# Hitachi_wind_main.net
KiCad netlist of a schematic drawn in Altium Designer
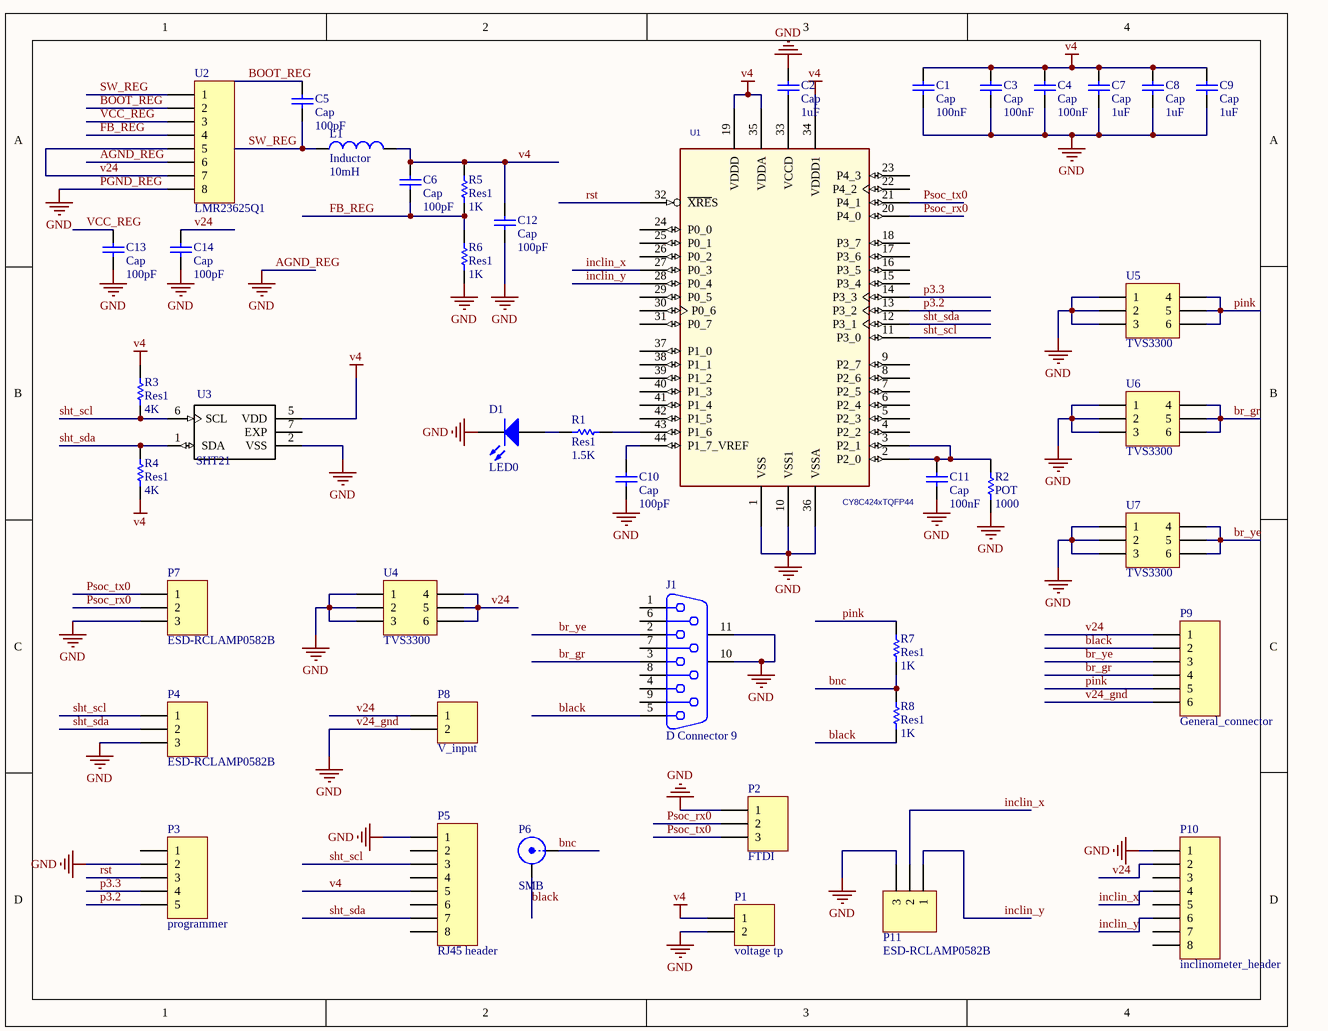
[diagram p0: Hitachi_wind_main.SchDoc]

(export (version "E")
  (design (tool "Eeschema 10.0.6"))
  (components
    (comp (ref "C1")
      (value "Cap")
      (footprint "Miscellaneous Devices:1608[0603]")
      (description "Capacitor")
      (fields (field (name "ALTIUM_VALUE") "100nF") (field (name "PUBLISHER") "Altium Limited"))
      (libsource (lib "Miscellaneous Devices") (part "Cap"))
    )
    (comp (ref "C2")
      (value "Cap")
      (footprint "Miscellaneous Devices:1608[0603]")
      (description "Capacitor")
      (fields (field (name "ALTIUM_VALUE") "1uF") (field (name "PUBLISHER") "Altium Limited"))
      (libsource (lib "Miscellaneous Devices") (part "Cap"))
    )
    (comp (ref "C3")
      (value "Cap")
      (footprint "Miscellaneous Devices:1608[0603]")
      (description "Capacitor")
      (fields (field (name "ALTIUM_VALUE") "100nF") (field (name "PUBLISHER") "Altium Limited"))
      (libsource (lib "Miscellaneous Devices") (part "Cap"))
    )
    (comp (ref "C4")
      (value "Cap")
      (footprint "Miscellaneous Devices:1608[0603]")
      (description "Capacitor")
      (fields (field (name "ALTIUM_VALUE") "100nF") (field (name "PUBLISHER") "Altium Limited"))
      (libsource (lib "Miscellaneous Devices") (part "Cap"))
    )
    (comp (ref "C5")
      (value "Cap")
      (footprint "Miscellaneous Devices:1608[0603]")
      (description "Capacitor")
      (fields (field (name "ALTIUM_VALUE") "100pF") (field (name "PUBLISHER") "Altium Limited"))
      (libsource (lib "Miscellaneous Devices") (part "Cap"))
    )
    (comp (ref "C6")
      (value "Cap")
      (footprint "Miscellaneous Devices:1608[0603]")
      (description "Capacitor")
      (fields (field (name "ALTIUM_VALUE") "100pF") (field (name "PUBLISHER") "Altium Limited"))
      (libsource (lib "Miscellaneous Devices") (part "Cap"))
    )
    (comp (ref "C7")
      (value "Cap")
      (footprint "Miscellaneous Devices:1608[0603]")
      (description "Capacitor")
      (fields (field (name "ALTIUM_VALUE") "1uF") (field (name "PUBLISHER") "Altium Limited"))
      (libsource (lib "Miscellaneous Devices") (part "Cap"))
    )
    (comp (ref "C8")
      (value "Cap")
      (footprint "Miscellaneous Devices:1608[0603]")
      (description "Capacitor")
      (fields (field (name "ALTIUM_VALUE") "1uF") (field (name "PUBLISHER") "Altium Limited"))
      (libsource (lib "Miscellaneous Devices") (part "Cap"))
    )
    (comp (ref "C9")
      (value "Cap")
      (footprint "Miscellaneous Devices:1608[0603]")
      (description "Capacitor")
      (fields (field (name "ALTIUM_VALUE") "1uF") (field (name "PUBLISHER") "Altium Limited"))
      (libsource (lib "Miscellaneous Devices") (part "Cap"))
    )
    (comp (ref "C10")
      (value "Cap")
      (footprint "Miscellaneous Devices:1608[0603]")
      (description "Capacitor")
      (fields (field (name "ALTIUM_VALUE") "100pF") (field (name "PUBLISHER") "Altium Limited"))
      (libsource (lib "Miscellaneous Devices") (part "Cap"))
    )
    (comp (ref "C11")
      (value "Cap")
      (footprint "Miscellaneous Devices:1608[0603]")
      (description "Capacitor")
      (fields (field (name "ALTIUM_VALUE") "100nF") (field (name "PUBLISHER") "Altium Limited"))
      (libsource (lib "Miscellaneous Devices") (part "Cap"))
    )
    (comp (ref "C12")
      (value "Cap")
      (footprint "Miscellaneous Devices:1608[0603]")
      (description "Capacitor")
      (fields (field (name "ALTIUM_VALUE") "100pF") (field (name "PUBLISHER") "Altium Limited"))
      (libsource (lib "Miscellaneous Devices") (part "Cap"))
    )
    (comp (ref "C13")
      (value "Cap")
      (footprint "Miscellaneous Devices:1608[0603]")
      (description "Capacitor")
      (fields (field (name "ALTIUM_VALUE") "100pF") (field (name "PUBLISHER") "Altium Limited"))
      (libsource (lib "Miscellaneous Devices") (part "Cap"))
    )
    (comp (ref "C14")
      (value "Cap")
      (footprint "Miscellaneous Devices:1608[0603]")
      (description "Capacitor")
      (fields (field (name "ALTIUM_VALUE") "100pF") (field (name "PUBLISHER") "Altium Limited"))
      (libsource (lib "Miscellaneous Devices") (part "Cap"))
    )
    (comp (ref "D1")
      (value "LED0")
      (footprint "3.2X1.6X1.1")
      (description "Typical INFRARED GaAs LED")
      (fields (field (name "PUBLISHER") "Altium Limited"))
      (libsource (lib "Miscellaneous Devices") (part "LED0"))
    )
    (comp (ref "J1")
      (value "D Connector 9")
      (footprint "DSUB1.385-2H9")
      (description "Receptacle Assembly, 9 Position, Right Angle")
      (fields (field (name "PUBLISHER") "Altium Limited"))
      (libsource (lib "Miscellaneous Connectors") (part "D Connector 9"))
    )
    (comp (ref "L1")
      (value "Inductor")
      (footprint "0402-A")
      (fields (field (name "ALTIUM_VALUE") "10mH") (field (name "PUBLISHER") "Altium Limited"))
      (libsource (lib "Miscellaneous Devices") (part "Inductor"))
    )
    (comp (ref "P1")
      (value "voltage tp")
      (footprint "HDR1X2")
      (description "Header, 2-Pin")
      (fields (field (name "PUBLISHER") "Altium Limited"))
      (libsource (lib "Miscellaneous Connectors") (part "Header 2"))
    )
    (comp (ref "P2")
      (value "FTDI")
      (footprint "HDR1X3")
      (description "Header, 3-Pin")
      (fields (field (name "PUBLISHER") "Altium Limited"))
      (libsource (lib "") (part "Header 3_1"))
    )
    (comp (ref "P3")
      (value "programmer")
      (footprint "HDR1X5")
      (description "Header, 5-Pin")
      (fields (field (name "PUBLISHER") "Altium Limited"))
      (libsource (lib "Miscellaneous Connectors") (part "Header 5"))
    )
    (comp (ref "P4")
      (value "ESD-RCLAMP0582B")
      (footprint "SC75:SC75")
      (description "Header, 3-Pin")
      (fields (field (name "PUBLISHER") "Altium Limited"))
      (libsource (lib "") (part "Header 3_1"))
    )
    (comp (ref "P5")
      (value "RJ45 header")
      (footprint "RJ-45 Header:RJ-45 Header")
      (description "Header, 8-Pin")
      (fields (field (name "PUBLISHER") "Altium Limited"))
      (libsource (lib "Miscellaneous Connectors") (part "Header 8"))
    )
    (comp (ref "P6")
      (value "SMB")
      (footprint "SMB_V-RJ45")
      (description "SMB Straight Connector")
      (fields (field (name "PUBLISHER") "Altium Limited"))
      (libsource (lib "Miscellaneous Connectors") (part "SMB"))
    )
    (comp (ref "P7")
      (value "ESD-RCLAMP0582B")
      (footprint "SC75:SC75")
      (description "Header, 3-Pin")
      (fields (field (name "PUBLISHER") "Altium Limited"))
      (libsource (lib "") (part "Header 3_1"))
    )
    (comp (ref "P8")
      (value "V_input")
      (footprint "HDR1X2")
      (description "Header, 2-Pin")
      (fields (field (name "PUBLISHER") "Altium Limited"))
      (libsource (lib "Miscellaneous Connectors") (part "Header 2"))
    )
    (comp (ref "P9")
      (value "General_connector")
      (footprint "HDR1X6")
      (description "Header, 6-Pin")
      (fields (field (name "PUBLISHER") "Altium Limited"))
      (libsource (lib "Miscellaneous Connectors") (part "Header 6"))
    )
    (comp (ref "P10")
      (value "inclinometer_header")
      (footprint "RJ-45 Header:RJ-45 Header")
      (description "Header, 8-Pin")
      (fields (field (name "PUBLISHER") "Altium Limited"))
      (libsource (lib "Miscellaneous Connectors") (part "Header 8"))
    )
    (comp (ref "P11")
      (value "ESD-RCLAMP0582B")
      (footprint "SC75:SC75")
      (description "Header, 3-Pin")
      (fields (field (name "PUBLISHER") "Altium Limited"))
      (libsource (lib "Miscellaneous Connectors") (part "Header 3"))
    )
    (comp (ref "R1")
      (value "Res1")
      (footprint "Miscellaneous Devices:6-0805_M")
      (description "Resistor")
      (fields (field (name "ALTIUM_VALUE") "1.5K") (field (name "PUBLISHER") "Altium Limited"))
      (libsource (lib "Miscellaneous Devices") (part "Res1"))
    )
    (comp (ref "R2")
      (value "POT")
      (footprint "Miscellaneous Devices:6-0805_M")
      (description "Resistor")
      (fields (field (name "ALTIUM_VALUE") "1000") (field (name "PUBLISHER") "Altium Limited"))
      (libsource (lib "Miscellaneous Devices") (part "Res1"))
    )
    (comp (ref "R3")
      (value "Res1")
      (footprint "Miscellaneous Devices:6-0805_M")
      (description "Resistor")
      (fields (field (name "ALTIUM_VALUE") "4K") (field (name "PUBLISHER") "Altium Limited"))
      (libsource (lib "Miscellaneous Devices") (part "Res1"))
    )
    (comp (ref "R4")
      (value "Res1")
      (footprint "Miscellaneous Devices:6-0805_M")
      (description "Resistor")
      (fields (field (name "ALTIUM_VALUE") "4K") (field (name "PUBLISHER") "Altium Limited"))
      (libsource (lib "Miscellaneous Devices") (part "Res1"))
    )
    (comp (ref "R5")
      (value "Res1")
      (footprint "Miscellaneous Devices:6-0805_M")
      (description "Resistor")
      (fields (field (name "ALTIUM_VALUE") "1K") (field (name "PUBLISHER") "Altium Limited"))
      (libsource (lib "Miscellaneous Devices") (part "Res1"))
    )
    (comp (ref "R6")
      (value "Res1")
      (footprint "Miscellaneous Devices:6-0805_M")
      (description "Resistor")
      (fields (field (name "ALTIUM_VALUE") "1K") (field (name "PUBLISHER") "Altium Limited"))
      (libsource (lib "Miscellaneous Devices") (part "Res1"))
    )
    (comp (ref "R7")
      (value "Res1")
      (footprint "Miscellaneous Devices:6-0805_M")
      (description "Resistor")
      (fields (field (name "ALTIUM_VALUE") "1K") (field (name "PUBLISHER") "Altium Limited"))
      (libsource (lib "Miscellaneous Devices") (part "Res1"))
    )
    (comp (ref "R8")
      (value "Res1")
      (footprint "Miscellaneous Devices:6-0805_M")
      (description "Resistor")
      (fields (field (name "ALTIUM_VALUE") "1K") (field (name "PUBLISHER") "Altium Limited"))
      (libsource (lib "Miscellaneous Devices") (part "Res1"))
    )
    (comp (ref "U1")
      (value "CY8C424xTQFP44")
      (footprint "TQFP50P900X900X160-48N")
      (fields (field (name "PART NUMBER") "CY8C424xTQFP44*"))
      (libsource (lib "PSOC4200M") (part "CY8C424xTQFP44"))
    )
    (comp (ref "U2")
      (value "LMR23625Q1")
      (footprint "ICs:SOIC-8")
      (description "Header, 8-Pin")
      (fields (field (name "PUBLISHER") "Altium Limited"))
      (libsource (lib "Miscellaneous Connectors") (part "Header 8"))
    )
    (comp (ref "U3")
      (value "SHT21")
      (footprint "SON100P300X300X110-7N")
      (description "SHT21 Series 3 V -40 to +125 Â°C Digital Humidity & Temperature Sensor IC - DFN-6")
      (fields (field (name "MF") "Sensirion"))
      (libsource (lib "SHT21") (part "SHT21"))
    )
    (comp (ref "U4")
      (value "TVS3300")
      (footprint "WSON:WSON-6_M")
      (description "Header, 3-Pin, Dual row")
      (fields (field (name "PUBLISHER") "Altium Limited"))
      (libsource (lib "Miscellaneous Connectors") (part "Header 3X2A"))
    )
    (comp (ref "U5")
      (value "TVS3300")
      (footprint "WSON:WSON-6_M")
      (description "Header, 3-Pin, Dual row")
      (fields (field (name "PUBLISHER") "Altium Limited"))
      (libsource (lib "Miscellaneous Connectors") (part "Header 3X2A"))
    )
    (comp (ref "U6")
      (value "TVS3300")
      (footprint "WSON:WSON-6_M")
      (description "Header, 3-Pin, Dual row")
      (fields (field (name "PUBLISHER") "Altium Limited"))
      (libsource (lib "Miscellaneous Connectors") (part "Header 3X2A"))
    )
    (comp (ref "U7")
      (value "TVS3300")
      (footprint "WSON:WSON-6_M")
      (description "Header, 3-Pin, Dual row")
      (fields (field (name "PUBLISHER") "Altium Limited"))
      (libsource (lib "Miscellaneous Connectors") (part "Header 3X2A"))
    )
  )
  (nets
    (net (code "1") (name "/BOOT_REG") (class "Default")
      (node (ref "C5") (pin "2") (pinfunction "2_2") (pintype "passive"))
      (node (ref "U2") (pin "2") (pinfunction "2_2") (pintype "passive"))
    )
    (net (code "2") (name "/FB_REG") (class "Default")
      (node (ref "C6") (pin "1") (pinfunction "1_1") (pintype "passive"))
      (node (ref "R5") (pin "1") (pinfunction "1_1") (pintype "passive"))
      (node (ref "R6") (pin "2") (pinfunction "2_2") (pintype "passive"))
      (node (ref "U2") (pin "4") (pinfunction "4_4") (pintype "passive"))
    )
    (net (code "3") (name "/Psoc_rx0") (class "Default")
      (node (ref "P2") (pin "2") (pinfunction "2_2") (pintype "passive"))
      (node (ref "P7") (pin "2") (pinfunction "2_2") (pintype "passive"))
      (node (ref "U1") (pin "20") (pinfunction "P4_0_20") (pintype "bidirectional"))
    )
    (net (code "4") (name "/Psoc_tx0") (class "Default")
      (node (ref "P2") (pin "3") (pinfunction "3_3") (pintype "passive"))
      (node (ref "P7") (pin "1") (pinfunction "1_1") (pintype "passive"))
      (node (ref "U1") (pin "21") (pinfunction "P4_1_21") (pintype "bidirectional"))
    )
    (net (code "5") (name "/SW_REG") (class "Default")
      (node (ref "C5") (pin "1") (pinfunction "1_1") (pintype "passive"))
      (node (ref "L1") (pin "1") (pinfunction "1_1") (pintype "passive"))
      (node (ref "U2") (pin "1") (pinfunction "1_1") (pintype "passive"))
    )
    (net (code "6") (name "/VCC_REG") (class "Default")
      (node (ref "C13") (pin "2") (pinfunction "2_2") (pintype "passive"))
      (node (ref "U2") (pin "3") (pinfunction "3_3") (pintype "passive"))
    )
    (net (code "7") (name "/black") (class "Default")
      (node (ref "J1") (pin "5") (pinfunction "5_5") (pintype "passive"))
      (node (ref "P6") (pin "2") (pinfunction "Y_2") (pintype "passive"))
      (node (ref "P9") (pin "2") (pinfunction "2_2") (pintype "passive"))
      (node (ref "R8") (pin "1") (pinfunction "1_1") (pintype "passive"))
    )
    (net (code "8") (name "/bnc") (class "Default")
      (node (ref "P6") (pin "1") (pinfunction "X_1") (pintype "passive"))
      (node (ref "R7") (pin "1") (pinfunction "1_1") (pintype "passive"))
      (node (ref "R8") (pin "2") (pinfunction "2_2") (pintype "passive"))
    )
    (net (code "9") (name "/br_gr") (class "Default")
      (node (ref "J1") (pin "3") (pinfunction "3_3") (pintype "passive"))
      (node (ref "P9") (pin "4") (pinfunction "4_4") (pintype "passive"))
      (node (ref "U6") (pin "4") (pinfunction "4_4") (pintype "passive"))
      (node (ref "U6") (pin "5") (pinfunction "5_5") (pintype "passive"))
      (node (ref "U6") (pin "6") (pinfunction "6_6") (pintype "passive"))
    )
    (net (code "10") (name "/br_ye") (class "Default")
      (node (ref "J1") (pin "2") (pinfunction "2_2") (pintype "passive"))
      (node (ref "P9") (pin "3") (pinfunction "3_3") (pintype "passive"))
      (node (ref "U7") (pin "4") (pinfunction "4_4") (pintype "passive"))
      (node (ref "U7") (pin "5") (pinfunction "5_5") (pintype "passive"))
      (node (ref "U7") (pin "6") (pinfunction "6_6") (pintype "passive"))
    )
    (net (code "11") (name "/inclin_x") (class "Default")
      (node (ref "P10") (pin "4") (pinfunction "4_4") (pintype "passive"))
      (node (ref "P11") (pin "2") (pinfunction "2_2") (pintype "passive"))
      (node (ref "U1") (pin "27") (pinfunction "P0_3_27") (pintype "bidirectional"))
    )
    (net (code "12") (name "/inclin_y") (class "Default")
      (node (ref "P10") (pin "6") (pinfunction "6_6") (pintype "passive"))
      (node (ref "P11") (pin "1") (pinfunction "1_1") (pintype "passive"))
      (node (ref "U1") (pin "28") (pinfunction "P0_4_28") (pintype "bidirectional"))
    )
    (net (code "13") (name "/p3.2") (class "Default")
      (node (ref "P3") (pin "5") (pinfunction "5_5") (pintype "passive"))
      (node (ref "U1") (pin "13") (pinfunction "P3_2_13") (pintype "bidirectional"))
    )
    (net (code "14") (name "/p3.3") (class "Default")
      (node (ref "P3") (pin "4") (pinfunction "4_4") (pintype "passive"))
      (node (ref "U1") (pin "14") (pinfunction "P3_3_14") (pintype "bidirectional"))
    )
    (net (code "15") (name "/pink") (class "Default")
      (node (ref "P9") (pin "5") (pinfunction "5_5") (pintype "passive"))
      (node (ref "R7") (pin "2") (pinfunction "2_2") (pintype "passive"))
      (node (ref "U5") (pin "4") (pinfunction "4_4") (pintype "passive"))
      (node (ref "U5") (pin "5") (pinfunction "5_5") (pintype "passive"))
      (node (ref "U5") (pin "6") (pinfunction "6_6") (pintype "passive"))
    )
    (net (code "16") (name "/rst") (class "Default")
      (node (ref "P3") (pin "3") (pinfunction "3_3") (pintype "passive"))
      (node (ref "U1") (pin "32") (pinfunction "~{XRE}S_32") (pintype "input"))
    )
    (net (code "17") (name "/sht_scl") (class "Default")
      (node (ref "P4") (pin "1") (pinfunction "1_1") (pintype "passive"))
      (node (ref "P5") (pin "3") (pinfunction "3_3") (pintype "passive"))
      (node (ref "R3") (pin "1") (pinfunction "1_1") (pintype "passive"))
      (node (ref "U1") (pin "11") (pinfunction "P3_0_11") (pintype "bidirectional"))
      (node (ref "U3") (pin "6") (pinfunction "SCL_6") (pintype "input"))
    )
    (net (code "18") (name "/sht_sda") (class "Default")
      (node (ref "P4") (pin "2") (pinfunction "2_2") (pintype "passive"))
      (node (ref "P5") (pin "7") (pinfunction "7_7") (pintype "passive"))
      (node (ref "R4") (pin "2") (pinfunction "2_2") (pintype "passive"))
      (node (ref "U1") (pin "12") (pinfunction "P3_1_12") (pintype "bidirectional"))
      (node (ref "U3") (pin "1") (pinfunction "SDA_1") (pintype "bidirectional"))
    )
    (net (code "19") (name "/v24") (class "Default")
      (node (ref "C14") (pin "2") (pinfunction "2_2") (pintype "passive"))
      (node (ref "P10") (pin "2") (pinfunction "2_2") (pintype "passive"))
      (node (ref "P8") (pin "1") (pinfunction "1_1") (pintype "passive"))
      (node (ref "P9") (pin "1") (pinfunction "1_1") (pintype "passive"))
      (node (ref "U2") (pin "5") (pinfunction "5_5") (pintype "passive"))
      (node (ref "U2") (pin "7") (pinfunction "7_7") (pintype "passive"))
      (node (ref "U4") (pin "4") (pinfunction "4_4") (pintype "passive"))
      (node (ref "U4") (pin "5") (pinfunction "5_5") (pintype "passive"))
      (node (ref "U4") (pin "6") (pinfunction "6_6") (pintype "passive"))
    )
    (net (code "20") (name "GND") (class "Default")
      (node (ref "C1") (pin "1") (pinfunction "1_1") (pintype "passive"))
      (node (ref "C10") (pin "1") (pinfunction "1_1") (pintype "passive"))
      (node (ref "C11") (pin "1") (pinfunction "1_1") (pintype "passive"))
      (node (ref "C12") (pin "1") (pinfunction "1_1") (pintype "passive"))
      (node (ref "C13") (pin "1") (pinfunction "1_1") (pintype "passive"))
      (node (ref "C14") (pin "1") (pinfunction "1_1") (pintype "passive"))
      (node (ref "C2") (pin "2") (pinfunction "2_2") (pintype "passive"))
      (node (ref "C3") (pin "1") (pinfunction "1_1") (pintype "passive"))
      (node (ref "C4") (pin "1") (pinfunction "1_1") (pintype "passive"))
      (node (ref "C7") (pin "1") (pinfunction "1_1") (pintype "passive"))
      (node (ref "C8") (pin "1") (pinfunction "1_1") (pintype "passive"))
      (node (ref "C9") (pin "1") (pinfunction "1_1") (pintype "passive"))
      (node (ref "D1") (pin "2") (pinfunction "K_2") (pintype "passive"))
      (node (ref "J1") (pin "10") (pinfunction "MH1_10") (pintype "passive"))
      (node (ref "J1") (pin "11") (pinfunction "MH2_11") (pintype "passive"))
      (node (ref "P1") (pin "2") (pinfunction "2_2") (pintype "passive"))
      (node (ref "P10") (pin "1") (pinfunction "1_1") (pintype "passive"))
      (node (ref "P11") (pin "3") (pinfunction "3_3") (pintype "passive"))
      (node (ref "P2") (pin "1") (pinfunction "1_1") (pintype "passive"))
      (node (ref "P3") (pin "2") (pinfunction "2_2") (pintype "passive"))
      (node (ref "P4") (pin "3") (pinfunction "3_3") (pintype "passive"))
      (node (ref "P5") (pin "1") (pinfunction "1_1") (pintype "passive"))
      (node (ref "P7") (pin "3") (pinfunction "3_3") (pintype "passive"))
      (node (ref "P8") (pin "2") (pinfunction "2_2") (pintype "passive"))
      (node (ref "P9") (pin "6") (pinfunction "6_6") (pintype "passive"))
      (node (ref "R2") (pin "1") (pinfunction "1_1") (pintype "passive"))
      (node (ref "R6") (pin "1") (pinfunction "1_1") (pintype "passive"))
      (node (ref "U1") (pin "1") (pinfunction "VSS_1") (pintype "power_in"))
      (node (ref "U1") (pin "10") (pinfunction "VSS1_10") (pintype "power_in"))
      (node (ref "U1") (pin "36") (pinfunction "VSSA_36") (pintype "power_in"))
      (node (ref "U2") (pin "6") (pinfunction "6_6") (pintype "passive"))
      (node (ref "U2") (pin "8") (pinfunction "8_8") (pintype "passive"))
      (node (ref "U3") (pin "2") (pinfunction "VSS_2") (pintype "power_in"))
      (node (ref "U4") (pin "1") (pinfunction "1_1") (pintype "passive"))
      (node (ref "U4") (pin "2") (pinfunction "2_2") (pintype "passive"))
      (node (ref "U4") (pin "3") (pinfunction "3_3") (pintype "passive"))
      (node (ref "U5") (pin "1") (pinfunction "1_1") (pintype "passive"))
      (node (ref "U5") (pin "2") (pinfunction "2_2") (pintype "passive"))
      (node (ref "U5") (pin "3") (pinfunction "3_3") (pintype "passive"))
      (node (ref "U6") (pin "1") (pinfunction "1_1") (pintype "passive"))
      (node (ref "U6") (pin "2") (pinfunction "2_2") (pintype "passive"))
      (node (ref "U6") (pin "3") (pinfunction "3_3") (pintype "passive"))
      (node (ref "U7") (pin "1") (pinfunction "1_1") (pintype "passive"))
      (node (ref "U7") (pin "2") (pinfunction "2_2") (pintype "passive"))
      (node (ref "U7") (pin "3") (pinfunction "3_3") (pintype "passive"))
    )
    (net (code "21") (name "Net-(D1-A)") (class "Default")
      (node (ref "D1") (pin "1") (pinfunction "A_1") (pintype "passive"))
      (node (ref "R1") (pin "1") (pinfunction "1_1") (pintype "passive"))
    )
    (net (code "22") (name "Net-(U1-P1_6)") (class "Default")
      (node (ref "R1") (pin "2") (pinfunction "2_2") (pintype "passive"))
      (node (ref "U1") (pin "43") (pinfunction "P1_6_43") (pintype "bidirectional"))
    )
    (net (code "23") (name "Net-(U1-P1_7_VREF)") (class "Default")
      (node (ref "C10") (pin "2") (pinfunction "2_2") (pintype "passive"))
      (node (ref "U1") (pin "44") (pinfunction "P1_7_VREF_44") (pintype "bidirectional"))
    )
    (net (code "24") (name "Net-(U1-P2_0)") (class "Default")
      (node (ref "C11") (pin "2") (pinfunction "2_2") (pintype "passive"))
      (node (ref "R2") (pin "2") (pinfunction "2_2") (pintype "passive"))
      (node (ref "U1") (pin "2") (pinfunction "P2_0_2") (pintype "bidirectional"))
      (node (ref "U1") (pin "3") (pinfunction "P2_1_3") (pintype "bidirectional"))
    )
    (net (code "25") (name "Net-(U1-VCCD)") (class "Default")
      (node (ref "C2") (pin "1") (pinfunction "1_1") (pintype "passive"))
      (node (ref "U1") (pin "33") (pinfunction "VCCD_33") (pintype "power_in"))
    )
    (net (code "26") (name "unconnected-(J1-Pad1)") (class "Default")
      (node (ref "J1") (pin "1") (pinfunction "1_1") (pintype "passive"))
    )
    (net (code "27") (name "unconnected-(J1-Pad4)") (class "Default")
      (node (ref "J1") (pin "4") (pinfunction "4_4") (pintype "passive"))
    )
    (net (code "28") (name "unconnected-(J1-Pad6)") (class "Default")
      (node (ref "J1") (pin "6") (pinfunction "6_6") (pintype "passive"))
    )
    (net (code "29") (name "unconnected-(J1-Pad7)") (class "Default")
      (node (ref "J1") (pin "7") (pinfunction "7_7") (pintype "passive"))
    )
    (net (code "30") (name "unconnected-(J1-Pad8)") (class "Default")
      (node (ref "J1") (pin "8") (pinfunction "8_8") (pintype "passive"))
    )
    (net (code "31") (name "unconnected-(J1-Pad9)") (class "Default")
      (node (ref "J1") (pin "9") (pinfunction "9_9") (pintype "passive"))
    )
    (net (code "32") (name "unconnected-(P3-Pad1)") (class "Default")
      (node (ref "P3") (pin "1") (pinfunction "1_1") (pintype "passive"))
    )
    (net (code "33") (name "unconnected-(P5-Pad2)") (class "Default")
      (node (ref "P5") (pin "2") (pinfunction "2_2") (pintype "passive"))
    )
    (net (code "34") (name "unconnected-(P5-Pad4)") (class "Default")
      (node (ref "P5") (pin "4") (pinfunction "4_4") (pintype "passive"))
    )
    (net (code "35") (name "unconnected-(P5-Pad6)") (class "Default")
      (node (ref "P5") (pin "6") (pinfunction "6_6") (pintype "passive"))
    )
    (net (code "36") (name "unconnected-(P5-Pad8)") (class "Default")
      (node (ref "P5") (pin "8") (pinfunction "8_8") (pintype "passive"))
    )
    (net (code "37") (name "unconnected-(P10-Pad3)") (class "Default")
      (node (ref "P10") (pin "3") (pinfunction "3_3") (pintype "passive"))
    )
    (net (code "38") (name "unconnected-(P10-Pad5)") (class "Default")
      (node (ref "P10") (pin "5") (pinfunction "5_5") (pintype "passive"))
    )
    (net (code "39") (name "unconnected-(P10-Pad7)") (class "Default")
      (node (ref "P10") (pin "7") (pinfunction "7_7") (pintype "passive"))
    )
    (net (code "40") (name "unconnected-(P10-Pad8)") (class "Default")
      (node (ref "P10") (pin "8") (pinfunction "8_8") (pintype "passive"))
    )
    (net (code "41") (name "unconnected-(U1-P0_0-Pad24)") (class "Default")
      (node (ref "U1") (pin "24") (pinfunction "P0_0_24") (pintype "bidirectional"))
    )
    (net (code "42") (name "unconnected-(U1-P0_1-Pad25)") (class "Default")
      (node (ref "U1") (pin "25") (pinfunction "P0_1_25") (pintype "bidirectional"))
    )
    (net (code "43") (name "unconnected-(U1-P0_2-Pad26)") (class "Default")
      (node (ref "U1") (pin "26") (pinfunction "P0_2_26") (pintype "bidirectional"))
    )
    (net (code "44") (name "unconnected-(U1-P0_5-Pad29)") (class "Default")
      (node (ref "U1") (pin "29") (pinfunction "P0_5_29") (pintype "bidirectional"))
    )
    (net (code "45") (name "unconnected-(U1-P0_6-Pad30)") (class "Default")
      (node (ref "U1") (pin "30") (pinfunction "P0_6_30") (pintype "bidirectional"))
    )
    (net (code "46") (name "unconnected-(U1-P0_7-Pad31)") (class "Default")
      (node (ref "U1") (pin "31") (pinfunction "P0_7_31") (pintype "bidirectional"))
    )
    (net (code "47") (name "unconnected-(U1-P1_0-Pad37)") (class "Default")
      (node (ref "U1") (pin "37") (pinfunction "P1_0_37") (pintype "bidirectional"))
    )
    (net (code "48") (name "unconnected-(U1-P1_1-Pad38)") (class "Default")
      (node (ref "U1") (pin "38") (pinfunction "P1_1_38") (pintype "bidirectional"))
    )
    (net (code "49") (name "unconnected-(U1-P1_2-Pad39)") (class "Default")
      (node (ref "U1") (pin "39") (pinfunction "P1_2_39") (pintype "bidirectional"))
    )
    (net (code "50") (name "unconnected-(U1-P1_3-Pad40)") (class "Default")
      (node (ref "U1") (pin "40") (pinfunction "P1_3_40") (pintype "bidirectional"))
    )
    (net (code "51") (name "unconnected-(U1-P1_4-Pad41)") (class "Default")
      (node (ref "U1") (pin "41") (pinfunction "P1_4_41") (pintype "bidirectional"))
    )
    (net (code "52") (name "unconnected-(U1-P1_5-Pad42)") (class "Default")
      (node (ref "U1") (pin "42") (pinfunction "P1_5_42") (pintype "bidirectional"))
    )
    (net (code "53") (name "unconnected-(U1-P2_2-Pad4)") (class "Default")
      (node (ref "U1") (pin "4") (pinfunction "P2_2_4") (pintype "bidirectional"))
    )
    (net (code "54") (name "unconnected-(U1-P2_3-Pad5)") (class "Default")
      (node (ref "U1") (pin "5") (pinfunction "P2_3_5") (pintype "bidirectional"))
    )
    (net (code "55") (name "unconnected-(U1-P2_4-Pad6)") (class "Default")
      (node (ref "U1") (pin "6") (pinfunction "P2_4_6") (pintype "bidirectional"))
    )
    (net (code "56") (name "unconnected-(U1-P2_5-Pad7)") (class "Default")
      (node (ref "U1") (pin "7") (pinfunction "P2_5_7") (pintype "bidirectional"))
    )
    (net (code "57") (name "unconnected-(U1-P2_6-Pad8)") (class "Default")
      (node (ref "U1") (pin "8") (pinfunction "P2_6_8") (pintype "bidirectional"))
    )
    (net (code "58") (name "unconnected-(U1-P2_7-Pad9)") (class "Default")
      (node (ref "U1") (pin "9") (pinfunction "P2_7_9") (pintype "bidirectional"))
    )
    (net (code "59") (name "unconnected-(U1-P3_4-Pad15)") (class "Default")
      (node (ref "U1") (pin "15") (pinfunction "P3_4_15") (pintype "bidirectional"))
    )
    (net (code "60") (name "unconnected-(U1-P3_5-Pad16)") (class "Default")
      (node (ref "U1") (pin "16") (pinfunction "P3_5_16") (pintype "bidirectional"))
    )
    (net (code "61") (name "unconnected-(U1-P3_6-Pad17)") (class "Default")
      (node (ref "U1") (pin "17") (pinfunction "P3_6_17") (pintype "bidirectional"))
    )
    (net (code "62") (name "unconnected-(U1-P3_7-Pad18)") (class "Default")
      (node (ref "U1") (pin "18") (pinfunction "P3_7_18") (pintype "bidirectional"))
    )
    (net (code "63") (name "unconnected-(U1-P4_2-Pad22)") (class "Default")
      (node (ref "U1") (pin "22") (pinfunction "P4_2_22") (pintype "bidirectional"))
    )
    (net (code "64") (name "unconnected-(U1-P4_3-Pad23)") (class "Default")
      (node (ref "U1") (pin "23") (pinfunction "P4_3_23") (pintype "bidirectional"))
    )
    (net (code "65") (name "unconnected-(U3-EXP-Pad7)") (class "Default")
      (node (ref "U3") (pin "7") (pinfunction "EXP_7") (pintype "power_in"))
    )
    (net (code "66") (name "v4") (class "Default")
      (node (ref "C1") (pin "2") (pinfunction "2_2") (pintype "passive"))
      (node (ref "C12") (pin "2") (pinfunction "2_2") (pintype "passive"))
      (node (ref "C3") (pin "2") (pinfunction "2_2") (pintype "passive"))
      (node (ref "C4") (pin "2") (pinfunction "2_2") (pintype "passive"))
      (node (ref "C6") (pin "2") (pinfunction "2_2") (pintype "passive"))
      (node (ref "C7") (pin "2") (pinfunction "2_2") (pintype "passive"))
      (node (ref "C8") (pin "2") (pinfunction "2_2") (pintype "passive"))
      (node (ref "C9") (pin "2") (pinfunction "2_2") (pintype "passive"))
      (node (ref "L1") (pin "2") (pinfunction "2_2") (pintype "passive"))
      (node (ref "P1") (pin "1") (pinfunction "1_1") (pintype "passive"))
      (node (ref "P5") (pin "5") (pinfunction "5_5") (pintype "passive"))
      (node (ref "R3") (pin "2") (pinfunction "2_2") (pintype "passive"))
      (node (ref "R4") (pin "1") (pinfunction "1_1") (pintype "passive"))
      (node (ref "R5") (pin "2") (pinfunction "2_2") (pintype "passive"))
      (node (ref "U1") (pin "19") (pinfunction "VDDD_19") (pintype "power_in"))
      (node (ref "U1") (pin "34") (pinfunction "VDDD1_34") (pintype "power_in"))
      (node (ref "U1") (pin "35") (pinfunction "VDDA_35") (pintype "power_in"))
      (node (ref "U3") (pin "5") (pinfunction "VDD_5") (pintype "power_in"))
    )
  )
)
